# routev7_5.net
KiCad netlist of a schematic drawn in EAGLE
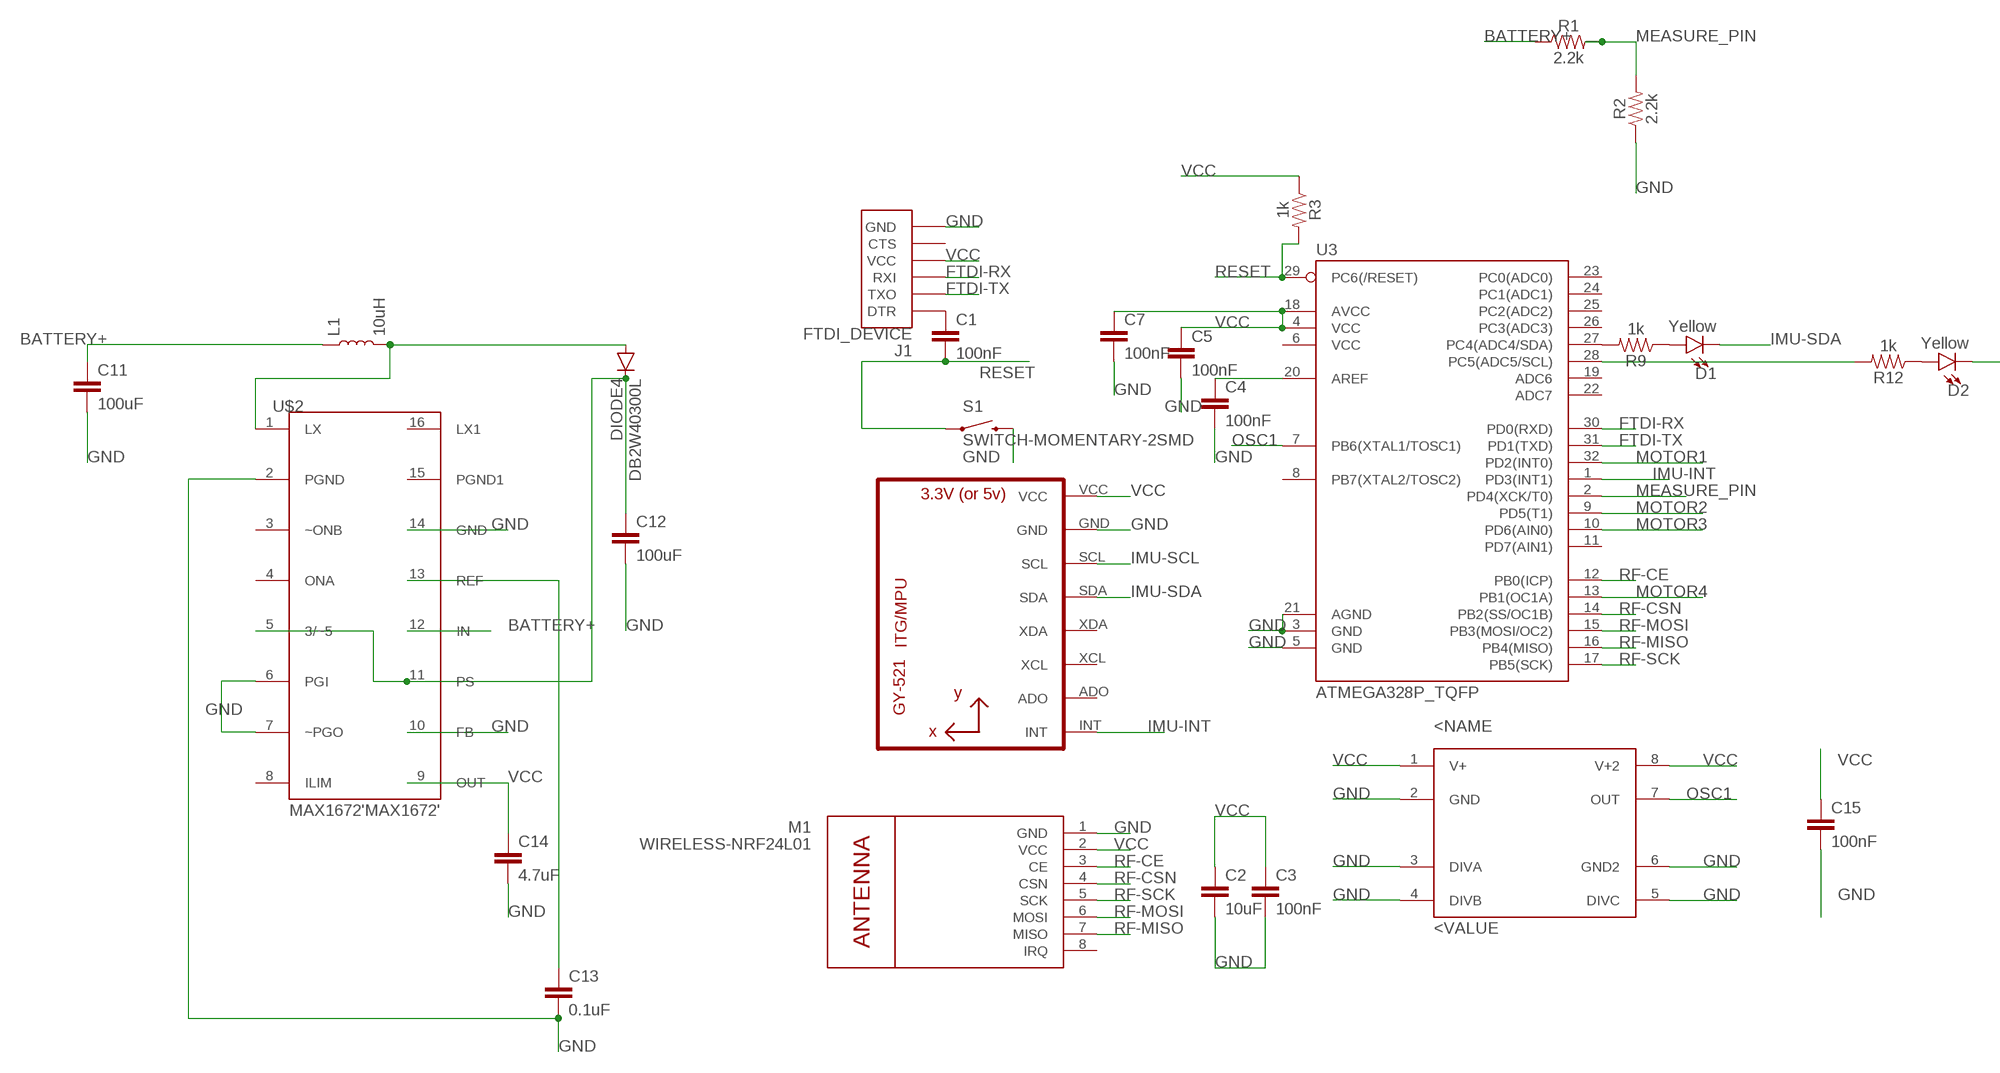
[diagram p0: schematic, sheet 1, part 1 of 2]
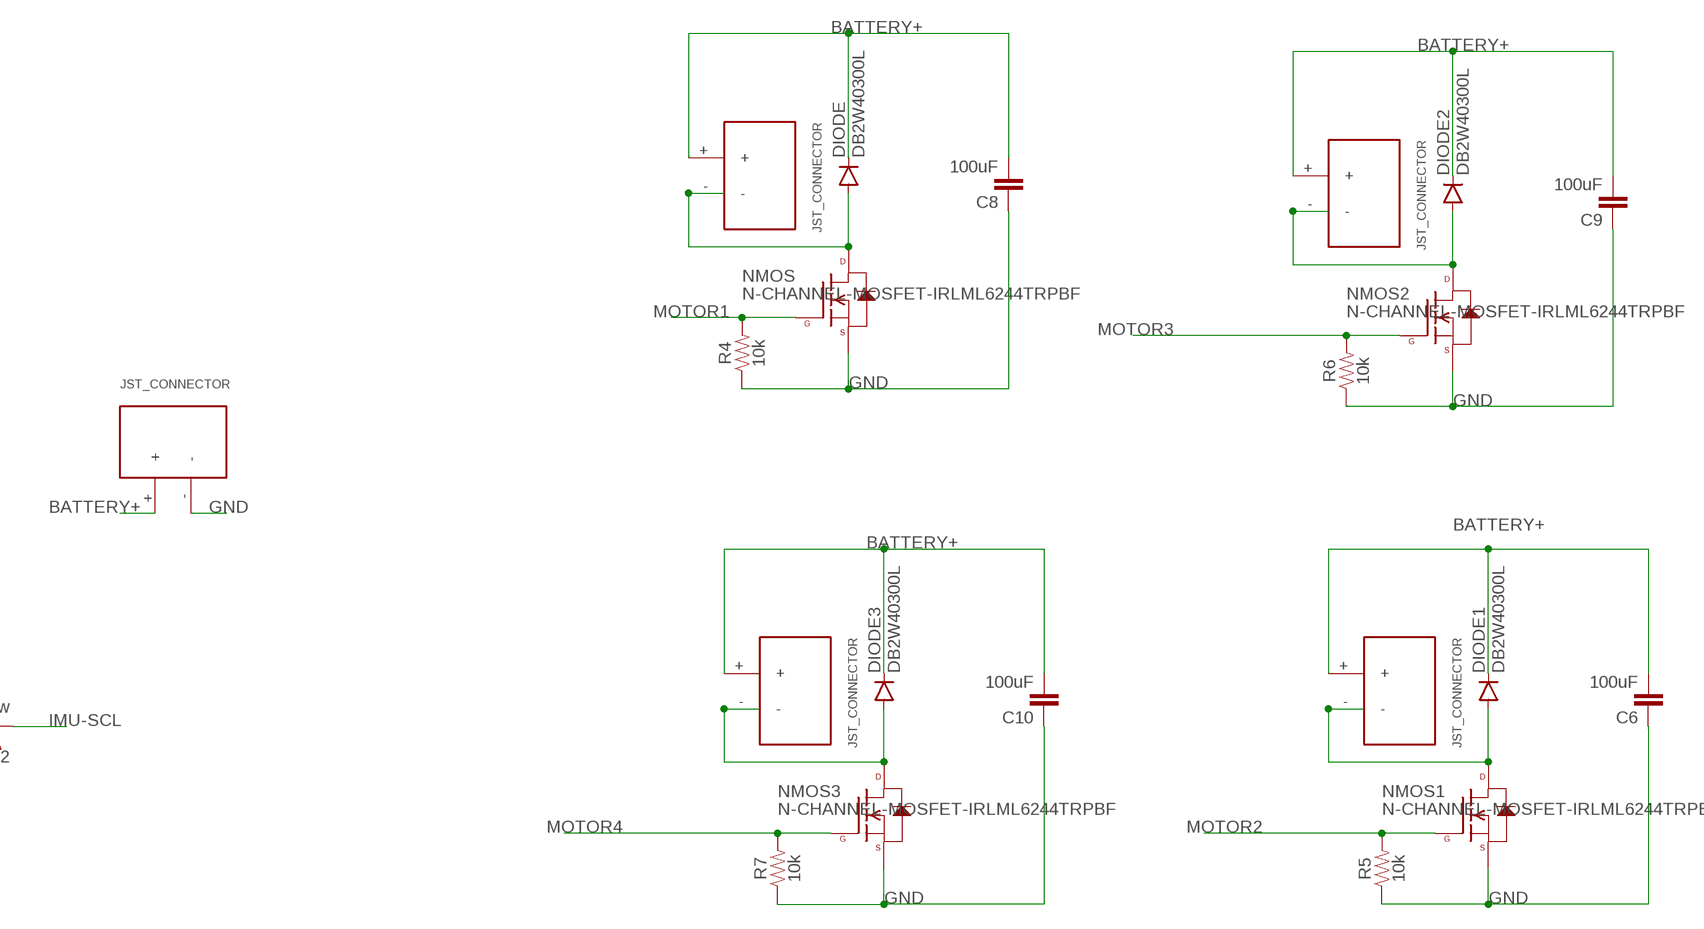
[diagram p1: schematic, sheet 1, part 2 of 2]

(export (version "E")
  (design (tool "Eeschema 10.0.6"))
  (components
    (comp (ref "C1")
      (value "100nF")
      (footprint "eagle-import:0603-CAP")
      (libsource (lib "eagle-import") (part "CAP0603-CAP"))
    )
    (comp (ref "C2")
      (value "10uF")
      (footprint "eagle-import:0603-CAP")
      (libsource (lib "eagle-import") (part "CAP0603-CAP"))
    )
    (comp (ref "C3")
      (value "100nF")
      (footprint "eagle-import:0603-CAP")
      (libsource (lib "eagle-import") (part "CAP0603-CAP"))
    )
    (comp (ref "C4")
      (value "100nF")
      (footprint "eagle-import:0603-CAP")
      (libsource (lib "eagle-import") (part "CAP0603-CAP"))
    )
    (comp (ref "C5")
      (value "100nF")
      (footprint "eagle-import:0603-CAP")
      (libsource (lib "eagle-import") (part "CAP0603-CAP"))
    )
    (comp (ref "C6")
      (value "100uF")
      (footprint "eagle-import:0603-CAP")
      (libsource (lib "eagle-import") (part "CAP0603-CAP"))
    )
    (comp (ref "C7")
      (value "100nF")
      (footprint "eagle-import:0603-CAP")
      (libsource (lib "eagle-import") (part "CAP0603-CAP"))
    )
    (comp (ref "C8")
      (value "100uF")
      (footprint "eagle-import:0603-CAP")
      (libsource (lib "eagle-import") (part "CAP0603-CAP"))
    )
    (comp (ref "C9")
      (value "100uF")
      (footprint "eagle-import:0603-CAP")
      (libsource (lib "eagle-import") (part "CAP0603-CAP"))
    )
    (comp (ref "C10")
      (value "100uF")
      (footprint "eagle-import:0603-CAP")
      (libsource (lib "eagle-import") (part "CAP0603-CAP"))
    )
    (comp (ref "C11")
      (value "100uF")
      (footprint "eagle-import:0603-CAP")
      (libsource (lib "eagle-import") (part "CAP0603-CAP"))
    )
    (comp (ref "C12")
      (value "100uF")
      (footprint "eagle-import:0603-CAP")
      (libsource (lib "eagle-import") (part "CAP0603-CAP"))
    )
    (comp (ref "C13")
      (value "0.1uF")
      (footprint "eagle-import:0603-CAP")
      (libsource (lib "eagle-import") (part "CAP0603-CAP"))
    )
    (comp (ref "C14")
      (value "4.7uF")
      (footprint "eagle-import:0603-CAP")
      (libsource (lib "eagle-import") (part "CAP0603-CAP"))
    )
    (comp (ref "C15")
      (value "100nF")
      (footprint "eagle-import:0603-CAP")
      (libsource (lib "eagle-import") (part "0.1UF-25V(+80/-20%)(0603)"))
    )
    (comp (ref "D1")
      (value "Yellow")
      (footprint "eagle-import:LED-1206")
      (libsource (lib "eagle-import") (part "LED-YELLOWLILYPAD"))
    )
    (comp (ref "D2")
      (value "Yellow")
      (footprint "eagle-import:LED-1206")
      (libsource (lib "eagle-import") (part "LED-YELLOWLILYPAD"))
    )
    (comp (ref "DIODE")
      (value "DB2W40300L")
      (footprint "eagle-import:MINI2-F3-B")
      (libsource (lib "eagle-import") (part "DB2W40300L"))
    )
    (comp (ref "DIODE1")
      (value "DB2W40300L")
      (footprint "eagle-import:MINI2-F3-B")
      (libsource (lib "eagle-import") (part "DB2W40300L"))
    )
    (comp (ref "DIODE2")
      (value "DB2W40300L")
      (footprint "eagle-import:MINI2-F3-B")
      (libsource (lib "eagle-import") (part "DB2W40300L"))
    )
    (comp (ref "DIODE3")
      (value "DB2W40300L")
      (footprint "eagle-import:MINI2-F3-B")
      (libsource (lib "eagle-import") (part "DB2W40300L"))
    )
    (comp (ref "DIODE4")
      (value "DB2W40300L")
      (footprint "eagle-import:MINI2-F3-B")
      (libsource (lib "eagle-import") (part "DB2W40300L"))
    )
    (comp (ref "J1")
      (value "FTDI_DEVICE")
      (footprint "eagle-import:FTDI_DEVICE_SIDE")
      (libsource (lib "eagle-import") (part "FTDI_DEVICE"))
    )
    (comp (ref "L1")
      (value "10uH")
      (footprint "eagle-import:0603")
      (libsource (lib "eagle-import") (part "INDUCTOR-0603-33NH"))
    )
    (comp (ref "M1")
      (value "WIRELESS-NRF24L01")
      (footprint "eagle-import:WIRELESS-NRF24L01")
      (libsource (lib "eagle-import") (part "WIRELESS-NRF24L01"))
    )
    (comp (ref "MOTOR")
      (value "JST_CONNECTOR_FEMALE")
      (footprint "eagle-import:JST_CONNECTOR_FEMALE")
      (libsource (lib "eagle-import") (part "JST_CONNECTOR_FEMALE"))
    )
    (comp (ref "MOTOR1")
      (value "JST_CONNECTOR_FEMALE")
      (footprint "eagle-import:JST_CONNECTOR_FEMALE")
      (libsource (lib "eagle-import") (part "JST_CONNECTOR_FEMALE"))
    )
    (comp (ref "MOTOR2")
      (value "JST_CONNECTOR_FEMALE")
      (footprint "eagle-import:JST_CONNECTOR_FEMALE")
      (libsource (lib "eagle-import") (part "JST_CONNECTOR_FEMALE"))
    )
    (comp (ref "MOTOR3")
      (value "JST_CONNECTOR_FEMALE")
      (footprint "eagle-import:JST_CONNECTOR_FEMALE")
      (libsource (lib "eagle-import") (part "JST_CONNECTOR_FEMALE"))
    )
    (comp (ref "NMOS")
      (value "N-CHANNEL-MOSFET-IRLML6244TRPBF")
      (footprint "eagle-import:SOT23-3")
      (libsource (lib "eagle-import") (part "N-CHANNEL-MOSFET-IRLML6244TRPBF"))
    )
    (comp (ref "NMOS1")
      (value "N-CHANNEL-MOSFET-IRLML6244TRPBF")
      (footprint "eagle-import:SOT23-3")
      (libsource (lib "eagle-import") (part "N-CHANNEL-MOSFET-IRLML6244TRPBF"))
    )
    (comp (ref "NMOS2")
      (value "N-CHANNEL-MOSFET-IRLML6244TRPBF")
      (footprint "eagle-import:SOT23-3")
      (libsource (lib "eagle-import") (part "N-CHANNEL-MOSFET-IRLML6244TRPBF"))
    )
    (comp (ref "NMOS3")
      (value "N-CHANNEL-MOSFET-IRLML6244TRPBF")
      (footprint "eagle-import:SOT23-3")
      (libsource (lib "eagle-import") (part "N-CHANNEL-MOSFET-IRLML6244TRPBF"))
    )
    (comp (ref "R1")
      (value "2.2k")
      (footprint "eagle-import:0603")
      (libsource (lib "eagle-import") (part "2.2KOHM-0603-1/10W-1%"))
    )
    (comp (ref "R2")
      (value "2.2k")
      (footprint "eagle-import:0603")
      (libsource (lib "eagle-import") (part "2.2KOHM-0603-1/10W-1%"))
    )
    (comp (ref "R3")
      (value "1k")
      (footprint "eagle-import:0603")
      (libsource (lib "eagle-import") (part "2.2KOHM-0603-1/10W-1%"))
    )
    (comp (ref "R4")
      (value "10k")
      (footprint "eagle-import:0603")
      (libsource (lib "eagle-import") (part "2.2KOHM-0603-1/10W-1%"))
    )
    (comp (ref "R5")
      (value "10k")
      (footprint "eagle-import:0603")
      (libsource (lib "eagle-import") (part "2.2KOHM-0603-1/10W-1%"))
    )
    (comp (ref "R6")
      (value "10k")
      (footprint "eagle-import:0603")
      (libsource (lib "eagle-import") (part "2.2KOHM-0603-1/10W-1%"))
    )
    (comp (ref "R7")
      (value "10k")
      (footprint "eagle-import:0603")
      (libsource (lib "eagle-import") (part "2.2KOHM-0603-1/10W-1%"))
    )
    (comp (ref "R9")
      (value "1k")
      (footprint "eagle-import:0603")
      (libsource (lib "eagle-import") (part "2.2KOHM-0603-1/10W-1%"))
    )
    (comp (ref "R12")
      (value "1k")
      (footprint "eagle-import:0603")
      (libsource (lib "eagle-import") (part "2.2KOHM-0603-1/10W-1%"))
    )
    (comp (ref "S1")
      (value "SWITCH-MOMENTARY-2SMD")
      (footprint "eagle-import:TACTILE-SWITCH-SMD")
      (libsource (lib "eagle-import") (part "SWITCH-MOMENTARY-2SMD"))
    )
    (comp (ref "U$1")
      (value "JST_CONNECTOR_FEMALE")
      (footprint "eagle-import:JST_CONNECTOR_FEMALE")
      (libsource (lib "eagle-import") (part "JST_CONNECTOR_FEMALE"))
    )
    (comp (ref "U$2")
      (value "MAX1672'MAX1672'")
      (footprint "eagle-import:21-0055H_16")
      (libsource (lib "eagle-import") (part "MAX1672'MAX1672'"))
    )
    (comp (ref "U$3")
      (value "LTC6930CMS8-8.19LTC6930CMS8-8.19")
      (footprint "eagle-import:SOP65P490X110-8N")
      (libsource (lib "eagle-import") (part "LTC6930CMS8-8.19LTC6930CMS8-8.19"))
    )
    (comp (ref "U2")
      (value "GY-521MPU6050")
      (footprint "eagle-import:GY-521")
      (libsource (lib "eagle-import") (part "GY-521MPU6050"))
    )
    (comp (ref "U3")
      (value "ATMEGA328P_TQFP")
      (footprint "eagle-import:TQFP32-08")
      (libsource (lib "eagle-import") (part "ATMEGA328P_TQFP"))
    )
  )
  (nets
    (net (code "1") (name "BATTERY+") (class "Default")
      (node (ref "C10") (pin "2") (pinfunction "2_2") (pintype "passive"))
      (node (ref "C11") (pin "1") (pinfunction "1_1") (pintype "passive"))
      (node (ref "C6") (pin "2") (pinfunction "2_2") (pintype "passive"))
      (node (ref "C8") (pin "2") (pinfunction "2_2") (pintype "passive"))
      (node (ref "C9") (pin "2") (pinfunction "2_2") (pintype "passive"))
      (node (ref "DIODE") (pin "NEG") (pinfunction "GPIN_NEG") (pintype "passive"))
      (node (ref "DIODE1") (pin "NEG") (pinfunction "GPIN_NEG") (pintype "passive"))
      (node (ref "DIODE2") (pin "NEG") (pinfunction "GPIN_NEG") (pintype "passive"))
      (node (ref "DIODE3") (pin "NEG") (pinfunction "GPIN_NEG") (pintype "passive"))
      (node (ref "L1") (pin "1") (pinfunction "1_1") (pintype "passive"))
      (node (ref "MOTOR") (pin "+") (pinfunction "+_+") (pintype "bidirectional"))
      (node (ref "MOTOR1") (pin "+") (pinfunction "+_+") (pintype "bidirectional"))
      (node (ref "MOTOR2") (pin "+") (pinfunction "+_+") (pintype "bidirectional"))
      (node (ref "MOTOR3") (pin "+") (pinfunction "+_+") (pintype "bidirectional"))
      (node (ref "R1") (pin "1") (pinfunction "1_1") (pintype "passive"))
      (node (ref "U$1") (pin "+") (pinfunction "+_+") (pintype "bidirectional"))
      (node (ref "U$2") (pin "12") (pinfunction "IN_12") (pintype "bidirectional"))
    )
    (net (code "2") (name "FTDI-RX") (class "Default")
      (node (ref "J1") (pin "P$3") (pinfunction "RXI_P$3") (pintype "bidirectional"))
      (node (ref "U3") (pin "30") (pinfunction "PD0(RXD)_30") (pintype "bidirectional"))
    )
    (net (code "3") (name "FTDI-TX") (class "Default")
      (node (ref "J1") (pin "P$2") (pinfunction "TXO_P$2") (pintype "bidirectional"))
      (node (ref "U3") (pin "31") (pinfunction "PD1(TXD)_31") (pintype "bidirectional"))
    )
    (net (code "4") (name "GND") (class "Default")
      (node (ref "C10") (pin "1") (pinfunction "1_1") (pintype "passive"))
      (node (ref "C11") (pin "2") (pinfunction "2_2") (pintype "passive"))
      (node (ref "C12") (pin "2") (pinfunction "2_2") (pintype "passive"))
      (node (ref "C13") (pin "2") (pinfunction "2_2") (pintype "passive"))
      (node (ref "C14") (pin "2") (pinfunction "2_2") (pintype "passive"))
      (node (ref "C15") (pin "2") (pinfunction "2_2") (pintype "passive"))
      (node (ref "C2") (pin "2") (pinfunction "2_2") (pintype "passive"))
      (node (ref "C3") (pin "2") (pinfunction "2_2") (pintype "passive"))
      (node (ref "C4") (pin "2") (pinfunction "2_2") (pintype "passive"))
      (node (ref "C5") (pin "2") (pinfunction "2_2") (pintype "passive"))
      (node (ref "C6") (pin "1") (pinfunction "1_1") (pintype "passive"))
      (node (ref "C7") (pin "2") (pinfunction "2_2") (pintype "passive"))
      (node (ref "C8") (pin "1") (pinfunction "1_1") (pintype "passive"))
      (node (ref "C9") (pin "1") (pinfunction "1_1") (pintype "passive"))
      (node (ref "J1") (pin "P$6") (pinfunction "GND_P$6") (pintype "bidirectional"))
      (node (ref "M1") (pin "1") (pinfunction "GND_1") (pintype "power_in"))
      (node (ref "NMOS") (pin "2") (pinfunction "S_2") (pintype "passive"))
      (node (ref "NMOS1") (pin "2") (pinfunction "S_2") (pintype "passive"))
      (node (ref "NMOS2") (pin "2") (pinfunction "S_2") (pintype "passive"))
      (node (ref "NMOS3") (pin "2") (pinfunction "S_2") (pintype "passive"))
      (node (ref "R2") (pin "1") (pinfunction "1_1") (pintype "passive"))
      (node (ref "R4") (pin "1") (pinfunction "1_1") (pintype "passive"))
      (node (ref "R5") (pin "1") (pinfunction "1_1") (pintype "passive"))
      (node (ref "R6") (pin "1") (pinfunction "1_1") (pintype "passive"))
      (node (ref "R7") (pin "1") (pinfunction "1_1") (pintype "passive"))
      (node (ref "S1") (pin "3") (pinfunction "2_3") (pintype "passive"))
      (node (ref "U$1") (pin "-") (pinfunction "-_-") (pintype "bidirectional"))
      (node (ref "U$2") (pin "10") (pinfunction "FB_10") (pintype "bidirectional"))
      (node (ref "U$2") (pin "14") (pinfunction "GND_14") (pintype "bidirectional"))
      (node (ref "U$2") (pin "2") (pinfunction "PGND_2") (pintype "bidirectional"))
      (node (ref "U$2") (pin "6") (pinfunction "PGI_6") (pintype "bidirectional"))
      (node (ref "U$2") (pin "7") (pinfunction "~{PGO}_7") (pintype "bidirectional"))
      (node (ref "U$3") (pin "2") (pinfunction "GND_2") (pintype "bidirectional"))
      (node (ref "U$3") (pin "3") (pinfunction "DIVA_3") (pintype "bidirectional"))
      (node (ref "U$3") (pin "4") (pinfunction "DIVB_4") (pintype "bidirectional"))
      (node (ref "U$3") (pin "5") (pinfunction "DIVC_5") (pintype "bidirectional"))
      (node (ref "U$3") (pin "6") (pinfunction "GND2_6") (pintype "bidirectional"))
      (node (ref "U2") (pin "GND") (pinfunction "GND_GND") (pintype "bidirectional"))
      (node (ref "U3") (pin "21") (pinfunction "AGND_21") (pintype "bidirectional"))
      (node (ref "U3") (pin "3") (pinfunction "GND_3") (pintype "bidirectional"))
      (node (ref "U3") (pin "5") (pinfunction "GND_5") (pintype "bidirectional"))
    )
    (net (code "5") (name "IMU-INT") (class "Default")
      (node (ref "U2") (pin "INT") (pinfunction "INT_INT") (pintype "bidirectional"))
      (node (ref "U3") (pin "1") (pinfunction "PD3(INT1)_1") (pintype "bidirectional"))
    )
    (net (code "6") (name "IMU-SCL") (class "Default")
      (node (ref "D2") (pin "C") (pinfunction "C_C") (pintype "passive"))
      (node (ref "U2") (pin "SCL") (pinfunction "SCL_SCL") (pintype "bidirectional"))
    )
    (net (code "7") (name "IMU-SDA") (class "Default")
      (node (ref "D1") (pin "C") (pinfunction "C_C") (pintype "passive"))
      (node (ref "U2") (pin "SDA") (pinfunction "SDA_SDA") (pintype "bidirectional"))
    )
    (net (code "8") (name "MEASURE_PIN") (class "Default")
      (node (ref "R1") (pin "2") (pinfunction "2_2") (pintype "passive"))
      (node (ref "R2") (pin "2") (pinfunction "2_2") (pintype "passive"))
      (node (ref "U3") (pin "2") (pinfunction "PD4(XCK/T0)_2") (pintype "bidirectional"))
    )
    (net (code "9") (name "MOTOR1") (class "Default")
      (node (ref "NMOS") (pin "1") (pinfunction "G_1") (pintype "passive"))
      (node (ref "R4") (pin "2") (pinfunction "2_2") (pintype "passive"))
      (node (ref "U3") (pin "32") (pinfunction "PD2(INT0)_32") (pintype "bidirectional"))
    )
    (net (code "10") (name "MOTOR2") (class "Default")
      (node (ref "NMOS1") (pin "1") (pinfunction "G_1") (pintype "passive"))
      (node (ref "R5") (pin "2") (pinfunction "2_2") (pintype "passive"))
      (node (ref "U3") (pin "9") (pinfunction "PD5(T1)_9") (pintype "bidirectional"))
    )
    (net (code "11") (name "MOTOR3") (class "Default")
      (node (ref "NMOS2") (pin "1") (pinfunction "G_1") (pintype "passive"))
      (node (ref "R6") (pin "2") (pinfunction "2_2") (pintype "passive"))
      (node (ref "U3") (pin "10") (pinfunction "PD6(AIN0)_10") (pintype "bidirectional"))
    )
    (net (code "12") (name "MOTOR4") (class "Default")
      (node (ref "NMOS3") (pin "1") (pinfunction "G_1") (pintype "passive"))
      (node (ref "R7") (pin "2") (pinfunction "2_2") (pintype "passive"))
      (node (ref "U3") (pin "13") (pinfunction "PB1(OC1A)_13") (pintype "bidirectional"))
    )
    (net (code "13") (name "Net-(D1-PadA)") (class "Default")
      (node (ref "D1") (pin "A") (pinfunction "A_A") (pintype "passive"))
      (node (ref "R9") (pin "1") (pinfunction "1_1") (pintype "passive"))
    )
    (net (code "14") (name "Net-(D2-PadA)") (class "Default")
      (node (ref "D2") (pin "A") (pinfunction "A_A") (pintype "passive"))
      (node (ref "R12") (pin "1") (pinfunction "1_1") (pintype "passive"))
    )
    (net (code "15") (name "Net-(DIODE-PPIN)") (class "Default")
      (node (ref "DIODE") (pin "POS") (pinfunction "PPIN_POS") (pintype "passive"))
      (node (ref "MOTOR") (pin "-") (pinfunction "-_-") (pintype "bidirectional"))
      (node (ref "NMOS") (pin "3") (pinfunction "D_3") (pintype "passive"))
    )
    (net (code "16") (name "Net-(DIODE1-PPIN)") (class "Default")
      (node (ref "DIODE1") (pin "POS") (pinfunction "PPIN_POS") (pintype "passive"))
      (node (ref "MOTOR1") (pin "-") (pinfunction "-_-") (pintype "bidirectional"))
      (node (ref "NMOS1") (pin "3") (pinfunction "D_3") (pintype "passive"))
    )
    (net (code "17") (name "Net-(DIODE2-PPIN)") (class "Default")
      (node (ref "DIODE2") (pin "POS") (pinfunction "PPIN_POS") (pintype "passive"))
      (node (ref "MOTOR2") (pin "-") (pinfunction "-_-") (pintype "bidirectional"))
      (node (ref "NMOS2") (pin "3") (pinfunction "D_3") (pintype "passive"))
    )
    (net (code "18") (name "Net-(DIODE3-PPIN)") (class "Default")
      (node (ref "DIODE3") (pin "POS") (pinfunction "PPIN_POS") (pintype "passive"))
      (node (ref "MOTOR3") (pin "-") (pinfunction "-_-") (pintype "bidirectional"))
      (node (ref "NMOS3") (pin "3") (pinfunction "D_3") (pintype "passive"))
    )
    (net (code "19") (name "Net-(DIODE4-GPIN)") (class "Default")
      (node (ref "C12") (pin "1") (pinfunction "1_1") (pintype "passive"))
      (node (ref "DIODE4") (pin "NEG") (pinfunction "GPIN_NEG") (pintype "passive"))
      (node (ref "U$2") (pin "11") (pinfunction "PS_11") (pintype "bidirectional"))
      (node (ref "U$2") (pin "5") (pinfunction "3/~{5}_5") (pintype "bidirectional"))
    )
    (net (code "20") (name "Net-(DIODE4-PPIN)") (class "Default")
      (node (ref "DIODE4") (pin "POS") (pinfunction "PPIN_POS") (pintype "passive"))
      (node (ref "L1") (pin "2") (pinfunction "2_2") (pintype "passive"))
      (node (ref "U$2") (pin "1") (pinfunction "LX_1") (pintype "bidirectional"))
    )
    (net (code "21") (name "Net-(J1-DTR)") (class "Default")
      (node (ref "C1") (pin "1") (pinfunction "1_1") (pintype "passive"))
      (node (ref "J1") (pin "P$1") (pinfunction "DTR_P$1") (pintype "bidirectional"))
    )
    (net (code "22") (name "Net-(U$2-REF)") (class "Default")
      (node (ref "C13") (pin "1") (pinfunction "1_1") (pintype "passive"))
      (node (ref "U$2") (pin "13") (pinfunction "REF_13") (pintype "bidirectional"))
    )
    (net (code "23") (name "Net-(U3-AREF)") (class "Default")
      (node (ref "C4") (pin "1") (pinfunction "1_1") (pintype "passive"))
      (node (ref "U3") (pin "20") (pinfunction "AREF_20") (pintype "bidirectional"))
    )
    (net (code "24") (name "Net-(U3-PC4(ADC4{slash}SDA))") (class "Default")
      (node (ref "R9") (pin "2") (pinfunction "2_2") (pintype "passive"))
      (node (ref "U3") (pin "27") (pinfunction "PC4(ADC4/SDA)_27") (pintype "bidirectional"))
    )
    (net (code "25") (name "Net-(U3-PC5(ADC5{slash}SCL))") (class "Default")
      (node (ref "R12") (pin "2") (pinfunction "2_2") (pintype "passive"))
      (node (ref "U3") (pin "28") (pinfunction "PC5(ADC5/SCL)_28") (pintype "bidirectional"))
    )
    (net (code "26") (name "OSC1") (class "Default")
      (node (ref "U$3") (pin "7") (pinfunction "OUT_7") (pintype "bidirectional"))
      (node (ref "U3") (pin "7") (pinfunction "PB6(XTAL1/TOSC1)_7") (pintype "bidirectional"))
    )
    (net (code "27") (name "RESET") (class "Default")
      (node (ref "C1") (pin "2") (pinfunction "2_2") (pintype "passive"))
      (node (ref "R3") (pin "2") (pinfunction "2_2") (pintype "passive"))
      (node (ref "S1") (pin "1") (pinfunction "1_1") (pintype "passive"))
      (node (ref "U3") (pin "29") (pinfunction "PC6(/RESET)_29") (pintype "bidirectional"))
    )
    (net (code "28") (name "RF-CE") (class "Default")
      (node (ref "M1") (pin "3") (pinfunction "CE_3") (pintype "bidirectional"))
      (node (ref "U3") (pin "12") (pinfunction "PB0(ICP)_12") (pintype "bidirectional"))
    )
    (net (code "29") (name "RF-CSN") (class "Default")
      (node (ref "M1") (pin "4") (pinfunction "CSN_4") (pintype "bidirectional"))
      (node (ref "U3") (pin "14") (pinfunction "PB2(SS/OC1B)_14") (pintype "bidirectional"))
    )
    (net (code "30") (name "RF-MISO") (class "Default")
      (node (ref "M1") (pin "7") (pinfunction "MISO_7") (pintype "bidirectional"))
      (node (ref "U3") (pin "16") (pinfunction "PB4(MISO)_16") (pintype "bidirectional"))
    )
    (net (code "31") (name "RF-MOSI") (class "Default")
      (node (ref "M1") (pin "6") (pinfunction "MOSI_6") (pintype "bidirectional"))
      (node (ref "U3") (pin "15") (pinfunction "PB3(MOSI/OC2)_15") (pintype "bidirectional"))
    )
    (net (code "32") (name "RF-SCK") (class "Default")
      (node (ref "M1") (pin "5") (pinfunction "SCK_5") (pintype "bidirectional"))
      (node (ref "U3") (pin "17") (pinfunction "PB5(SCK)_17") (pintype "bidirectional"))
    )
    (net (code "33") (name "VCC") (class "Default")
      (node (ref "C14") (pin "1") (pinfunction "1_1") (pintype "passive"))
      (node (ref "C15") (pin "1") (pinfunction "1_1") (pintype "passive"))
      (node (ref "C2") (pin "1") (pinfunction "1_1") (pintype "passive"))
      (node (ref "C3") (pin "1") (pinfunction "1_1") (pintype "passive"))
      (node (ref "C5") (pin "1") (pinfunction "1_1") (pintype "passive"))
      (node (ref "C7") (pin "1") (pinfunction "1_1") (pintype "passive"))
      (node (ref "J1") (pin "P$4") (pinfunction "VCC_P$4") (pintype "bidirectional"))
      (node (ref "M1") (pin "2") (pinfunction "VCC_2") (pintype "power_in"))
      (node (ref "R3") (pin "1") (pinfunction "1_1") (pintype "passive"))
      (node (ref "U$2") (pin "9") (pinfunction "OUT_9") (pintype "bidirectional"))
      (node (ref "U$3") (pin "1") (pinfunction "V+_1") (pintype "bidirectional"))
      (node (ref "U$3") (pin "8") (pinfunction "V+2_8") (pintype "bidirectional"))
      (node (ref "U2") (pin "VCC") (pinfunction "VCC_VCC") (pintype "bidirectional"))
      (node (ref "U3") (pin "18") (pinfunction "AVCC_18") (pintype "bidirectional"))
      (node (ref "U3") (pin "4") (pinfunction "VCC_4") (pintype "bidirectional"))
    )
    (net (code "34") (name "unconnected-(J1-CTS-PadP$5)") (class "Default")
      (node (ref "J1") (pin "P$5") (pinfunction "CTS_P$5") (pintype "bidirectional"))
    )
    (net (code "35") (name "unconnected-(M1-IRQ-Pad8)") (class "Default")
      (node (ref "M1") (pin "8") (pinfunction "IRQ_8") (pintype "bidirectional"))
    )
    (net (code "36") (name "unconnected-(U$2-ILIM-Pad8)") (class "Default")
      (node (ref "U$2") (pin "8") (pinfunction "ILIM_8") (pintype "bidirectional"))
    )
    (net (code "37") (name "unconnected-(U$2-LX1-Pad16)") (class "Default")
      (node (ref "U$2") (pin "16") (pinfunction "LX1_16") (pintype "bidirectional"))
    )
    (net (code "38") (name "unconnected-(U$2-ONA-Pad4)") (class "Default")
      (node (ref "U$2") (pin "4") (pinfunction "ONA_4") (pintype "bidirectional"))
    )
    (net (code "39") (name "unconnected-(U$2-PGND1-Pad15)") (class "Default")
      (node (ref "U$2") (pin "15") (pinfunction "PGND1_15") (pintype "bidirectional"))
    )
    (net (code "40") (name "unconnected-(U$2-~{ONB}-Pad3)") (class "Default")
      (node (ref "U$2") (pin "3") (pinfunction "~{ONB}_3") (pintype "bidirectional"))
    )
    (net (code "41") (name "unconnected-(U2-PadADO)") (class "Default")
      (node (ref "U2") (pin "ADO") (pinfunction "ADO_ADO") (pintype "bidirectional"))
    )
    (net (code "42") (name "unconnected-(U2-PadXCL)") (class "Default")
      (node (ref "U2") (pin "XCL") (pinfunction "XCL_XCL") (pintype "bidirectional"))
    )
    (net (code "43") (name "unconnected-(U2-PadXDA)") (class "Default")
      (node (ref "U2") (pin "XDA") (pinfunction "XDA_XDA") (pintype "bidirectional"))
    )
    (net (code "44") (name "unconnected-(U3-ADC6-Pad19)") (class "Default")
      (node (ref "U3") (pin "19") (pinfunction "ADC6_19") (pintype "bidirectional"))
    )
    (net (code "45") (name "unconnected-(U3-ADC7-Pad22)") (class "Default")
      (node (ref "U3") (pin "22") (pinfunction "ADC7_22") (pintype "bidirectional"))
    )
    (net (code "46") (name "unconnected-(U3-PB7(XTAL2{slash}TOSC2)-Pad8)") (class "Default")
      (node (ref "U3") (pin "8") (pinfunction "PB7(XTAL2/TOSC2)_8") (pintype "bidirectional"))
    )
    (net (code "47") (name "unconnected-(U3-PC0(ADC0)-Pad23)") (class "Default")
      (node (ref "U3") (pin "23") (pinfunction "PC0(ADC0)_23") (pintype "bidirectional"))
    )
    (net (code "48") (name "unconnected-(U3-PC1(ADC1)-Pad24)") (class "Default")
      (node (ref "U3") (pin "24") (pinfunction "PC1(ADC1)_24") (pintype "bidirectional"))
    )
    (net (code "49") (name "unconnected-(U3-PC2(ADC2)-Pad25)") (class "Default")
      (node (ref "U3") (pin "25") (pinfunction "PC2(ADC2)_25") (pintype "bidirectional"))
    )
    (net (code "50") (name "unconnected-(U3-PC3(ADC3)-Pad26)") (class "Default")
      (node (ref "U3") (pin "26") (pinfunction "PC3(ADC3)_26") (pintype "bidirectional"))
    )
    (net (code "51") (name "unconnected-(U3-PD7(AIN1)-Pad11)") (class "Default")
      (node (ref "U3") (pin "11") (pinfunction "PD7(AIN1)_11") (pintype "bidirectional"))
    )
    (net (code "52") (name "unconnected-(U3-VCC-Pad6)") (class "Default")
      (node (ref "U3") (pin "6") (pinfunction "VCC_6") (pintype "bidirectional"))
    )
  )
)
